# tablet.net
KiCad netlist of a schematic drawn in EAGLE
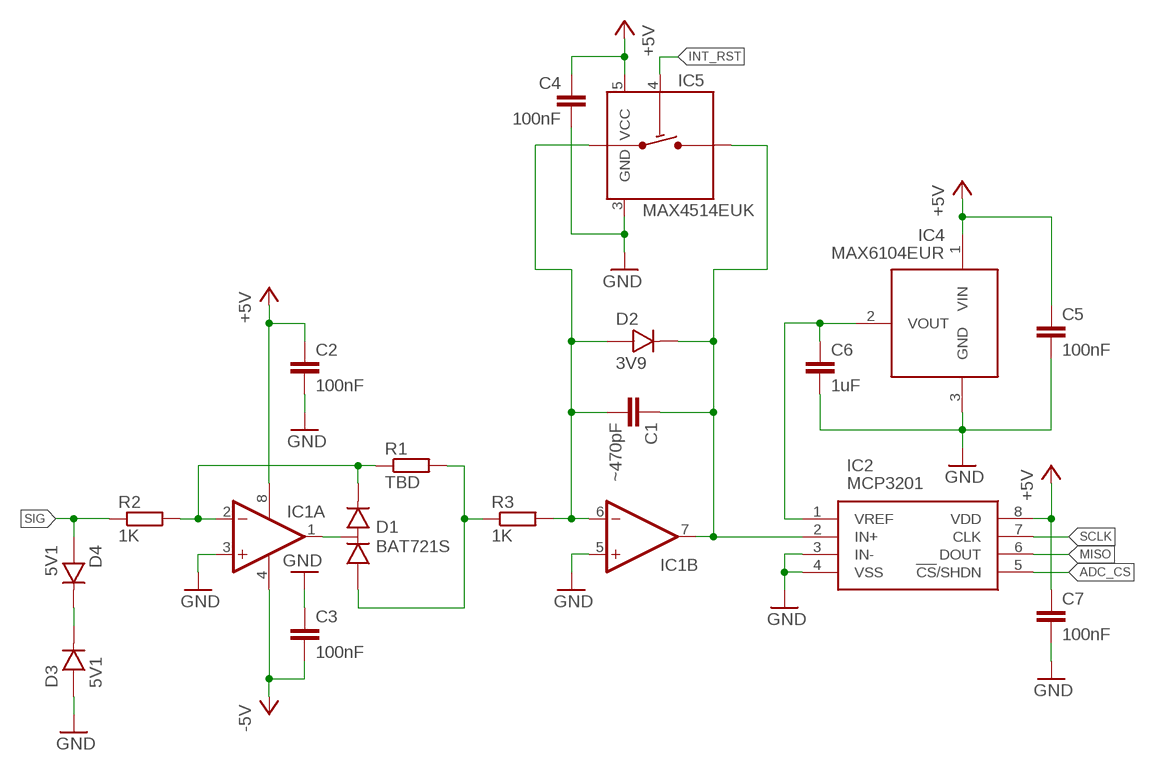
[diagram p0: schematic, sheet 1]

(export (version "E")
  (design (tool "Eeschema 10.0.6"))
  (components
    (comp (ref "C1")
      (value "~470pF")
      (footprint "eagle-import:0603")
      (libsource (lib "eagle-import") (part "C0603"))
    )
    (comp (ref "C2")
      (value "100nF")
      (footprint "eagle-import:0603")
      (libsource (lib "eagle-import") (part "C0603"))
    )
    (comp (ref "C3")
      (value "100nF")
      (footprint "eagle-import:0603")
      (libsource (lib "eagle-import") (part "C0603"))
    )
    (comp (ref "C4")
      (value "100nF")
      (footprint "eagle-import:0603")
      (libsource (lib "eagle-import") (part "C0603"))
    )
    (comp (ref "C5")
      (value "100nF")
      (footprint "eagle-import:0603")
      (libsource (lib "eagle-import") (part "C0603"))
    )
    (comp (ref "C6")
      (value "1uF")
      (footprint "eagle-import:0603")
      (libsource (lib "eagle-import") (part "C0603"))
    )
    (comp (ref "C7")
      (value "100nF")
      (footprint "eagle-import:0603")
      (libsource (lib "eagle-import") (part "C0603"))
    )
    (comp (ref "D1")
      (value "BAT721S")
      (footprint "eagle-import:SOT23_3")
      (libsource (lib "eagle-import") (part "D2_SERIESSOT23"))
    )
    (comp (ref "D2")
      (value "3V9")
      (footprint "eagle-import:SOD323")
      (libsource (lib "eagle-import") (part "DSOD323"))
    )
    (comp (ref "D3")
      (value "5V1")
      (footprint "eagle-import:SOD323")
      (libsource (lib "eagle-import") (part "DSOD323"))
    )
    (comp (ref "D4")
      (value "5V1")
      (footprint "eagle-import:SOD323")
      (libsource (lib "eagle-import") (part "DSOD323"))
    )
    (comp (ref "IC1")
      (value "OPAMP_DUALSOIC8")
      (footprint "eagle-import:SOIC8")
      (libsource (lib "eagle-import") (part "OPAMP_DUALSOIC8"))
    )
    (comp (ref "IC2")
      (value "MCP3201")
      (footprint "eagle-import:SOIC8")
      (libsource (lib "eagle-import") (part "MCP3201"))
    )
    (comp (ref "IC4")
      (value "MAX6104EUR")
      (footprint "eagle-import:SOT23_3")
      (libsource (lib "eagle-import") (part "MAX6104EUR"))
    )
    (comp (ref "IC5")
      (value "MAX4514EUK")
      (footprint "eagle-import:SOT23_5")
      (libsource (lib "eagle-import") (part "MAX4514EUK"))
    )
    (comp (ref "R1")
      (value "TBD")
      (footprint "eagle-import:0603")
      (libsource (lib "eagle-import") (part "R0603"))
    )
    (comp (ref "R2")
      (value "1K")
      (footprint "eagle-import:0603")
      (libsource (lib "eagle-import") (part "R0603"))
    )
    (comp (ref "R3")
      (value "1K")
      (footprint "eagle-import:0603")
      (libsource (lib "eagle-import") (part "R0603"))
    )
  )
  (nets
    (net (code "1") (name "+5V") (class "Default")
      (node (ref "C2") (pin "1") (pinfunction "1_1") (pintype "passive"))
      (node (ref "C4") (pin "1") (pinfunction "1_1") (pintype "passive"))
      (node (ref "C5") (pin "1") (pinfunction "1_1") (pintype "passive"))
      (node (ref "C7") (pin "1") (pinfunction "1_1") (pintype "passive"))
      (node (ref "IC1") (pin "8") (pinfunction "V+_8") (pintype "power_in"))
      (node (ref "IC2") (pin "8") (pinfunction "VDD_8") (pintype "power_in"))
      (node (ref "IC4") (pin "1") (pinfunction "VIN_1") (pintype "bidirectional"))
      (node (ref "IC5") (pin "5") (pinfunction "VCC_5") (pintype "power_in"))
    )
    (net (code "2") (name "-5V") (class "Default")
      (node (ref "C3") (pin "2") (pinfunction "2_2") (pintype "passive"))
      (node (ref "IC1") (pin "4") (pinfunction "V-_4") (pintype "power_in"))
    )
    (net (code "3") (name "ADC_CS") (class "Default")
      (node (ref "IC2") (pin "5") (pinfunction "~{CS}/SHDN_5") (pintype "input"))
    )
    (net (code "4") (name "GND") (class "Default")
      (node (ref "C2") (pin "2") (pinfunction "2_2") (pintype "passive"))
      (node (ref "C3") (pin "1") (pinfunction "1_1") (pintype "passive"))
      (node (ref "C4") (pin "2") (pinfunction "2_2") (pintype "passive"))
      (node (ref "C5") (pin "2") (pinfunction "2_2") (pintype "passive"))
      (node (ref "C6") (pin "2") (pinfunction "2_2") (pintype "passive"))
      (node (ref "C7") (pin "2") (pinfunction "2_2") (pintype "passive"))
      (node (ref "D3") (pin "1") (pinfunction "1_1") (pintype "passive"))
      (node (ref "IC1") (pin "3") (pinfunction "+IN_3") (pintype "input"))
      (node (ref "IC1") (pin "5") (pinfunction "+IN_5") (pintype "input"))
      (node (ref "IC2") (pin "3") (pinfunction "IN-_3") (pintype "input"))
      (node (ref "IC2") (pin "4") (pinfunction "VSS_4") (pintype "power_in"))
      (node (ref "IC4") (pin "3") (pinfunction "GND_3") (pintype "bidirectional"))
      (node (ref "IC5") (pin "3") (pinfunction "GND_3") (pintype "power_in"))
    )
    (net (code "5") (name "INT_RST") (class "Default")
      (node (ref "IC5") (pin "4") (pinfunction "IN_4") (pintype "input"))
    )
    (net (code "6") (name "MISO") (class "Default")
      (node (ref "IC2") (pin "6") (pinfunction "DOUT_6") (pintype "output"))
    )
    (net (code "7") (name "Net-(D1-A)") (class "Default")
      (node (ref "D1") (pin "1") (pinfunction "A_1") (pintype "passive"))
      (node (ref "R1") (pin "2") (pinfunction "2_2") (pintype "passive"))
      (node (ref "R3") (pin "1") (pinfunction "1_1") (pintype "passive"))
    )
    (net (code "8") (name "Net-(D1-C)") (class "Default")
      (node (ref "D1") (pin "2") (pinfunction "C_2") (pintype "passive"))
      (node (ref "IC1") (pin "2") (pinfunction "-IN_2") (pintype "input"))
      (node (ref "R1") (pin "1") (pinfunction "1_1") (pintype "passive"))
      (node (ref "R2") (pin "2") (pinfunction "2_2") (pintype "passive"))
    )
    (net (code "9") (name "Net-(D1-COM)") (class "Default")
      (node (ref "D1") (pin "3") (pinfunction "COM_3") (pintype "passive"))
      (node (ref "IC1") (pin "1") (pinfunction "OUT_1") (pintype "output"))
    )
    (net (code "10") (name "Net-(D3-Pad2)") (class "Default")
      (node (ref "D3") (pin "2") (pinfunction "2_2") (pintype "passive"))
      (node (ref "D4") (pin "2") (pinfunction "2_2") (pintype "passive"))
    )
    (net (code "11") (name "Net-(IC1B--IN)") (class "Default")
      (node (ref "C1") (pin "2") (pinfunction "2_2") (pintype "passive"))
      (node (ref "D2") (pin "1") (pinfunction "1_1") (pintype "passive"))
      (node (ref "IC1") (pin "6") (pinfunction "-IN_6") (pintype "input"))
      (node (ref "IC5") (pin "1") (pinfunction "COM_1") (pintype "bidirectional"))
      (node (ref "R3") (pin "2") (pinfunction "2_2") (pintype "passive"))
    )
    (net (code "12") (name "Net-(IC1B-OUT)") (class "Default")
      (node (ref "C1") (pin "1") (pinfunction "1_1") (pintype "passive"))
      (node (ref "D2") (pin "2") (pinfunction "2_2") (pintype "passive"))
      (node (ref "IC1") (pin "7") (pinfunction "OUT_7") (pintype "output"))
      (node (ref "IC2") (pin "2") (pinfunction "IN+_2") (pintype "input"))
      (node (ref "IC5") (pin "2") (pinfunction "NO_2") (pintype "bidirectional"))
    )
    (net (code "13") (name "Net-(IC2-VREF)") (class "Default")
      (node (ref "C6") (pin "1") (pinfunction "1_1") (pintype "passive"))
      (node (ref "IC2") (pin "1") (pinfunction "VREF_1") (pintype "input"))
      (node (ref "IC4") (pin "2") (pinfunction "VOUT_2") (pintype "bidirectional"))
    )
    (net (code "14") (name "SCLK") (class "Default")
      (node (ref "IC2") (pin "7") (pinfunction "CLK_7") (pintype "input"))
    )
    (net (code "15") (name "SIG") (class "Default")
      (node (ref "D4") (pin "1") (pinfunction "1_1") (pintype "passive"))
      (node (ref "R2") (pin "1") (pinfunction "1_1") (pintype "passive"))
    )
  )
)
